# lvc-sampler.net
KiCad netlist of a schematic drawn in EAGLE
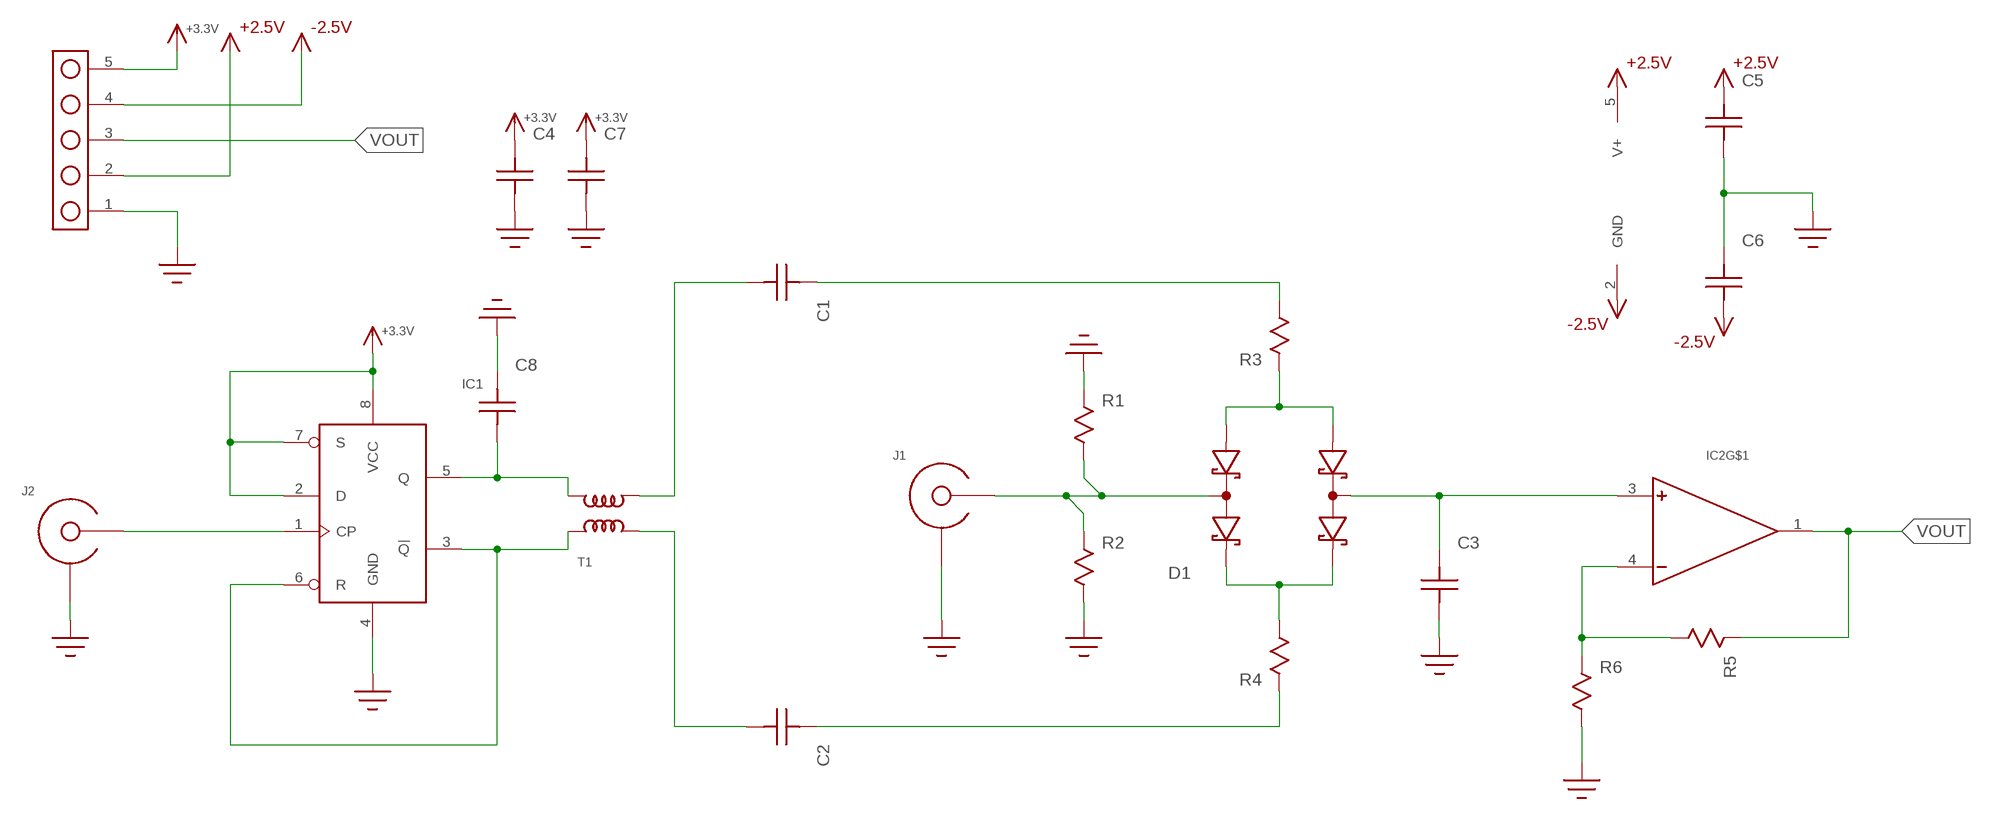
[diagram p0: schematic, sheet 1]

(export (version "E")
  (design (tool "Eeschema 10.0.6"))
  (components
    (comp (ref "C1")
      (value "C0603")
      (footprint "eagle-import:C0603")
      (libsource (lib "eagle-import") (part "C0603"))
    )
    (comp (ref "C2")
      (value "C0603")
      (footprint "eagle-import:C0603")
      (libsource (lib "eagle-import") (part "C0603"))
    )
    (comp (ref "C3")
      (value "C0603")
      (footprint "eagle-import:C0603")
      (libsource (lib "eagle-import") (part "C0603"))
    )
    (comp (ref "C4")
      (value "C0603")
      (footprint "eagle-import:C0603")
      (libsource (lib "eagle-import") (part "C0603"))
    )
    (comp (ref "C5")
      (value "C0603")
      (footprint "eagle-import:C0603")
      (libsource (lib "eagle-import") (part "C0603"))
    )
    (comp (ref "C6")
      (value "C0603")
      (footprint "eagle-import:C0603")
      (libsource (lib "eagle-import") (part "C0603"))
    )
    (comp (ref "C7")
      (value "C0603")
      (footprint "eagle-import:C0603")
      (libsource (lib "eagle-import") (part "C0603"))
    )
    (comp (ref "C8")
      (value "C0603")
      (footprint "eagle-import:C0603")
      (libsource (lib "eagle-import") (part "C0603"))
    )
    (comp (ref "D1")
      (value "SMS3923-081")
      (footprint "eagle-import:SC-88")
      (libsource (lib "eagle-import") (part "SMS3923-081"))
    )
    (comp (ref "IC1")
      (value "74LVC2G74")
      (footprint "eagle-import:SSOP8")
      (libsource (lib "eagle-import") (part "74LVC2G74"))
    )
    (comp (ref "IC2")
      (value "MCP601")
      (footprint "eagle-import:SOT23-5")
      (libsource (lib "eagle-import") (part "MCP601"))
    )
    (comp (ref "J1")
      (value "SMA-EDGE-LAUNCH4020_TAPER")
      (footprint "eagle-import:SMA_EDGE_LAUNCH_2L_4020_TAPER")
      (libsource (lib "eagle-import") (part "SMA-EDGE-LAUNCH4020_TAPER"))
    )
    (comp (ref "J2")
      (value "SMA-EDGE-LAUNCH4020_TAPER")
      (footprint "eagle-import:SMA_EDGE_LAUNCH_2L_4020_TAPER")
      (libsource (lib "eagle-import") (part "SMA-EDGE-LAUNCH4020_TAPER"))
    )
    (comp (ref "J3")
      (value "HEADER_5PIN")
      (footprint "eagle-import:HEADER_5PIN")
      (libsource (lib "eagle-import") (part "HEADER_5PIN"))
    )
    (comp (ref "R1")
      (value "R0603")
      (footprint "eagle-import:R0603")
      (libsource (lib "eagle-import") (part "R0603"))
    )
    (comp (ref "R2")
      (value "R0603")
      (footprint "eagle-import:R0603")
      (libsource (lib "eagle-import") (part "R0603"))
    )
    (comp (ref "R3")
      (value "R0603")
      (footprint "eagle-import:R0603")
      (libsource (lib "eagle-import") (part "R0603"))
    )
    (comp (ref "R4")
      (value "R0603")
      (footprint "eagle-import:R0603")
      (libsource (lib "eagle-import") (part "R0603"))
    )
    (comp (ref "R5")
      (value "R0603")
      (footprint "eagle-import:R0603")
      (libsource (lib "eagle-import") (part "R0603"))
    )
    (comp (ref "R6")
      (value "R0603")
      (footprint "eagle-import:R0603")
      (libsource (lib "eagle-import") (part "R0603"))
    )
    (comp (ref "T1")
      (value "MABA007159")
      (footprint "eagle-import:MABAES0061")
      (libsource (lib "eagle-import") (part "MABA007159"))
    )
  )
  (nets
    (net (code "1") (name "+2.5V") (class "Default")
      (node (ref "C5") (pin "P$2") (pinfunction "P$2_P$2") (pintype "bidirectional"))
      (node (ref "IC2") (pin "5") (pinfunction "V+_5") (pintype "bidirectional"))
      (node (ref "J3") (pin "2") (pinfunction "2_2") (pintype "bidirectional"))
    )
    (net (code "2") (name "+3.3V") (class "Default")
      (node (ref "C4") (pin "P$2") (pinfunction "P$2_P$2") (pintype "bidirectional"))
      (node (ref "C7") (pin "P$2") (pinfunction "P$2_P$2") (pintype "bidirectional"))
      (node (ref "IC1") (pin "2") (pinfunction "D_2") (pintype "bidirectional"))
      (node (ref "IC1") (pin "7") (pinfunction "S_7") (pintype "bidirectional"))
      (node (ref "IC1") (pin "8") (pinfunction "VCC_8") (pintype "bidirectional"))
      (node (ref "J3") (pin "5") (pinfunction "5_5") (pintype "bidirectional"))
    )
    (net (code "3") (name "-2.5V") (class "Default")
      (node (ref "C6") (pin "P$1") (pinfunction "P$1_P$1") (pintype "bidirectional"))
      (node (ref "IC2") (pin "2") (pinfunction "GND_2") (pintype "bidirectional"))
      (node (ref "J3") (pin "4") (pinfunction "4_4") (pintype "bidirectional"))
    )
    (net (code "4") (name "GND") (class "Default")
      (node (ref "C3") (pin "P$1") (pinfunction "P$1_P$1") (pintype "bidirectional"))
      (node (ref "C4") (pin "P$1") (pinfunction "P$1_P$1") (pintype "bidirectional"))
      (node (ref "C5") (pin "P$1") (pinfunction "P$1_P$1") (pintype "bidirectional"))
      (node (ref "C6") (pin "P$2") (pinfunction "P$2_P$2") (pintype "bidirectional"))
      (node (ref "C7") (pin "P$1") (pinfunction "P$1_P$1") (pintype "bidirectional"))
      (node (ref "C8") (pin "P$2") (pinfunction "P$2_P$2") (pintype "bidirectional"))
      (node (ref "IC1") (pin "4") (pinfunction "GND_4") (pintype "bidirectional"))
      (node (ref "J1") (pin "BOTTOM_GND") (pinfunction "SHIELD_BOTTOM_GND") (pintype "bidirectional"))
      (node (ref "J1") (pin "GND@1") (pinfunction "SHIELD_GND@1") (pintype "bidirectional"))
      (node (ref "J1") (pin "GND@14") (pinfunction "SHIELD_GND@14") (pintype "bidirectional"))
      (node (ref "J1") (pin "GND@15") (pinfunction "SHIELD_GND@15") (pintype "bidirectional"))
      (node (ref "J1") (pin "GND@16") (pinfunction "SHIELD_GND@16") (pintype "bidirectional"))
      (node (ref "J1") (pin "GND@17") (pinfunction "SHIELD_GND@17") (pintype "bidirectional"))
      (node (ref "J1") (pin "GND@2") (pinfunction "SHIELD_GND@2") (pintype "bidirectional"))
      (node (ref "J1") (pin "GND@3") (pinfunction "SHIELD_GND@3") (pintype "bidirectional"))
      (node (ref "J1") (pin "GND@4") (pinfunction "SHIELD_GND@4") (pintype "bidirectional"))
      (node (ref "J1") (pin "GND@5") (pinfunction "SHIELD_GND@5") (pintype "bidirectional"))
      (node (ref "J1") (pin "GND@6") (pinfunction "SHIELD_GND@6") (pintype "bidirectional"))
      (node (ref "J1") (pin "GND@7") (pinfunction "SHIELD_GND@7") (pintype "bidirectional"))
      (node (ref "J1") (pin "GND@8") (pinfunction "SHIELD_GND@8") (pintype "bidirectional"))
      (node (ref "J1") (pin "GND_PAD1") (pinfunction "SHIELD_GND_PAD1") (pintype "bidirectional"))
      (node (ref "J1") (pin "GND_PAD2") (pinfunction "SHIELD_GND_PAD2") (pintype "bidirectional"))
      (node (ref "J1") (pin "P$1") (pinfunction "SHIELD_P$1") (pintype "bidirectional"))
      (node (ref "J1") (pin "P$2") (pinfunction "SHIELD_P$2") (pintype "bidirectional"))
      (node (ref "J2") (pin "BOTTOM_GND") (pinfunction "SHIELD_BOTTOM_GND") (pintype "bidirectional"))
      (node (ref "J2") (pin "GND@1") (pinfunction "SHIELD_GND@1") (pintype "bidirectional"))
      (node (ref "J2") (pin "GND@14") (pinfunction "SHIELD_GND@14") (pintype "bidirectional"))
      (node (ref "J2") (pin "GND@15") (pinfunction "SHIELD_GND@15") (pintype "bidirectional"))
      (node (ref "J2") (pin "GND@16") (pinfunction "SHIELD_GND@16") (pintype "bidirectional"))
      (node (ref "J2") (pin "GND@17") (pinfunction "SHIELD_GND@17") (pintype "bidirectional"))
      (node (ref "J2") (pin "GND@2") (pinfunction "SHIELD_GND@2") (pintype "bidirectional"))
      (node (ref "J2") (pin "GND@3") (pinfunction "SHIELD_GND@3") (pintype "bidirectional"))
      (node (ref "J2") (pin "GND@4") (pinfunction "SHIELD_GND@4") (pintype "bidirectional"))
      (node (ref "J2") (pin "GND@5") (pinfunction "SHIELD_GND@5") (pintype "bidirectional"))
      (node (ref "J2") (pin "GND@6") (pinfunction "SHIELD_GND@6") (pintype "bidirectional"))
      (node (ref "J2") (pin "GND@7") (pinfunction "SHIELD_GND@7") (pintype "bidirectional"))
      (node (ref "J2") (pin "GND@8") (pinfunction "SHIELD_GND@8") (pintype "bidirectional"))
      (node (ref "J2") (pin "GND_PAD1") (pinfunction "SHIELD_GND_PAD1") (pintype "bidirectional"))
      (node (ref "J2") (pin "GND_PAD2") (pinfunction "SHIELD_GND_PAD2") (pintype "bidirectional"))
      (node (ref "J2") (pin "P$1") (pinfunction "SHIELD_P$1") (pintype "bidirectional"))
      (node (ref "J2") (pin "P$2") (pinfunction "SHIELD_P$2") (pintype "bidirectional"))
      (node (ref "J3") (pin "1") (pinfunction "1_1") (pintype "bidirectional"))
      (node (ref "R1") (pin "P$1") (pinfunction "P$3_P$1") (pintype "bidirectional"))
      (node (ref "R2") (pin "P$2") (pinfunction "P$4_P$2") (pintype "bidirectional"))
      (node (ref "R6") (pin "P$2") (pinfunction "P$4_P$2") (pintype "bidirectional"))
    )
    (net (code "5") (name "Net-(C1-PadP$1)") (class "Default")
      (node (ref "C1") (pin "P$1") (pinfunction "P$1_P$1") (pintype "bidirectional"))
      (node (ref "T1") (pin "3") (pinfunction "3_3") (pintype "bidirectional"))
    )
    (net (code "6") (name "Net-(C2-PadP$1)") (class "Default")
      (node (ref "C2") (pin "P$1") (pinfunction "P$1_P$1") (pintype "bidirectional"))
      (node (ref "T1") (pin "1") (pinfunction "1_1") (pintype "bidirectional"))
    )
    (net (code "7") (name "Net-(D1-ANODE0)") (class "Default")
      (node (ref "D1") (pin "1") (pinfunction "ANODE0_1") (pintype "bidirectional"))
      (node (ref "D1") (pin "6") (pinfunction "ANODE1_6") (pintype "bidirectional"))
      (node (ref "R3") (pin "P$1") (pinfunction "P$3_P$1") (pintype "bidirectional"))
    )
    (net (code "8") (name "Net-(D1-CATHODE0)") (class "Default")
      (node (ref "D1") (pin "3") (pinfunction "CATHODE0_3") (pintype "bidirectional"))
      (node (ref "D1") (pin "4") (pinfunction "CATHODE1_4") (pintype "bidirectional"))
      (node (ref "R4") (pin "P$2") (pinfunction "P$4_P$2") (pintype "bidirectional"))
    )
    (net (code "9") (name "Net-(D1-COMMON0)") (class "Default")
      (node (ref "D1") (pin "2") (pinfunction "COMMON0_2") (pintype "bidirectional"))
      (node (ref "J1") (pin "CENTER@1") (pinfunction "CENTER_CENTER@1") (pintype "bidirectional"))
      (node (ref "R1") (pin "P$2") (pinfunction "P$4_P$2") (pintype "bidirectional"))
      (node (ref "R2") (pin "P$1") (pinfunction "P$3_P$1") (pintype "bidirectional"))
    )
    (net (code "10") (name "Net-(D1-COMMON1)") (class "Default")
      (node (ref "C3") (pin "P$2") (pinfunction "P$2_P$2") (pintype "bidirectional"))
      (node (ref "D1") (pin "5") (pinfunction "COMMON1_5") (pintype "bidirectional"))
      (node (ref "IC2") (pin "3") (pinfunction "+_3") (pintype "bidirectional"))
    )
    (net (code "11") (name "Net-(IC1-CP)") (class "Default")
      (node (ref "IC1") (pin "1") (pinfunction "CP_1") (pintype "bidirectional"))
      (node (ref "J2") (pin "CENTER@1") (pinfunction "CENTER_CENTER@1") (pintype "bidirectional"))
    )
    (net (code "12") (name "Net-(IC1-Q)") (class "Default")
      (node (ref "C8") (pin "P$1") (pinfunction "P$1_P$1") (pintype "bidirectional"))
      (node (ref "IC1") (pin "5") (pinfunction "Q_5") (pintype "bidirectional"))
      (node (ref "T1") (pin "4") (pinfunction "4_4") (pintype "bidirectional"))
    )
    (net (code "13") (name "Net-(IC1-R)") (class "Default")
      (node (ref "IC1") (pin "3") (pinfunction "~{Q}_3") (pintype "bidirectional"))
      (node (ref "IC1") (pin "6") (pinfunction "R_6") (pintype "bidirectional"))
      (node (ref "T1") (pin "5") (pinfunction "5_5") (pintype "bidirectional"))
    )
    (net (code "14") (name "Net-(IC2A--)") (class "Default")
      (node (ref "IC2") (pin "4") (pinfunction "-_4") (pintype "bidirectional"))
      (node (ref "R5") (pin "P$2") (pinfunction "P$4_P$2") (pintype "bidirectional"))
      (node (ref "R6") (pin "P$1") (pinfunction "P$3_P$1") (pintype "bidirectional"))
    )
    (net (code "15") (name "Net-(R3-P$4)") (class "Default")
      (node (ref "C1") (pin "P$2") (pinfunction "P$2_P$2") (pintype "bidirectional"))
      (node (ref "R3") (pin "P$2") (pinfunction "P$4_P$2") (pintype "bidirectional"))
    )
    (net (code "16") (name "Net-(R4-P$3)") (class "Default")
      (node (ref "C2") (pin "P$2") (pinfunction "P$2_P$2") (pintype "bidirectional"))
      (node (ref "R4") (pin "P$1") (pinfunction "P$3_P$1") (pintype "bidirectional"))
    )
    (net (code "17") (name "VOUT") (class "Default")
      (node (ref "IC2") (pin "1") (pinfunction "OUT_1") (pintype "bidirectional"))
      (node (ref "J3") (pin "3") (pinfunction "3_3") (pintype "bidirectional"))
      (node (ref "R5") (pin "P$1") (pinfunction "P$3_P$1") (pintype "bidirectional"))
    )
  )
)
